# docking_connector_v2.net
KiCad netlist of a schematic drawn in Altium Designer
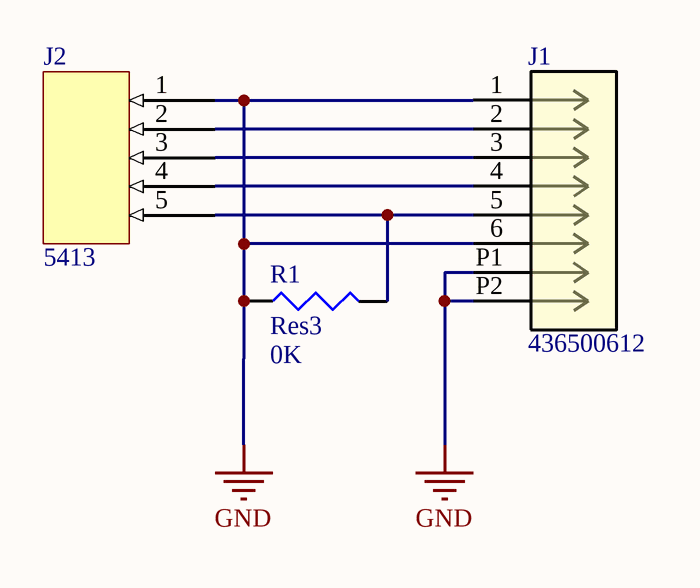
[diagram p0: docking_connector_v2.SchDoc]

(export (version "E")
  (design (tool "Eeschema 10.0.6"))
  (components
    (comp (ref "J1")
      (value "436500612")
      (footprint "swarm_crawler_pcb:CON_436500612")
      (description "No Description Available")
      (fields (field (name "COPYRIGHT") "Copyright (C) 2023 Ultra Librarian. All rights reserved."))
      (libsource (lib "swarm_crawler_sch") (part "436500612"))
    )
    (comp (ref "J2") (value "5413") (footprint "5413") (libsource (lib "swarm_crawler_sch") (part "5413")))
    (comp (ref "R1")
      (value "Res3")
      (footprint "J1-0603")
      (description "Resistor")
      (fields (field (name "ALTIUM_VALUE") "0K") (field (name "PUBLISHER") "Altium Limited"))
      (libsource (lib "Miscellaneous Devices") (part "Res3"))
    )
  )
  (nets
    (net (code "1") (name "GND") (class "Default")
      (node (ref "J1") (pin "1") (pinfunction "1_1") (pintype "passive"))
      (node (ref "J1") (pin "6") (pinfunction "6_6") (pintype "passive"))
      (node (ref "J1") (pin "P1") (pinfunction "P1_P1") (pintype "passive"))
      (node (ref "J1") (pin "P2") (pinfunction "P2_P2") (pintype "passive"))
      (node (ref "J2") (pin "1") (pintype "input"))
      (node (ref "R1") (pin "1") (pinfunction "1_1") (pintype "passive"))
    )
    (net (code "2") (name "Net-(J1-Pad2)") (class "Default")
      (node (ref "J1") (pin "2") (pinfunction "2_2") (pintype "passive"))
      (node (ref "J2") (pin "2") (pintype "input"))
    )
    (net (code "3") (name "Net-(J1-Pad3)") (class "Default")
      (node (ref "J1") (pin "3") (pinfunction "3_3") (pintype "passive"))
      (node (ref "J2") (pin "3") (pintype "input"))
    )
    (net (code "4") (name "Net-(J1-Pad4)") (class "Default")
      (node (ref "J1") (pin "4") (pinfunction "4_4") (pintype "passive"))
      (node (ref "J2") (pin "4") (pintype "input"))
    )
    (net (code "5") (name "Net-(J1-Pad5)") (class "Default")
      (node (ref "J1") (pin "5") (pinfunction "5_5") (pintype "passive"))
      (node (ref "J2") (pin "5") (pintype "input"))
      (node (ref "R1") (pin "2") (pinfunction "2_2") (pintype "passive"))
    )
  )
)
